# CANageddonBus.net
KiCad netlist of a schematic drawn in EasyEDA
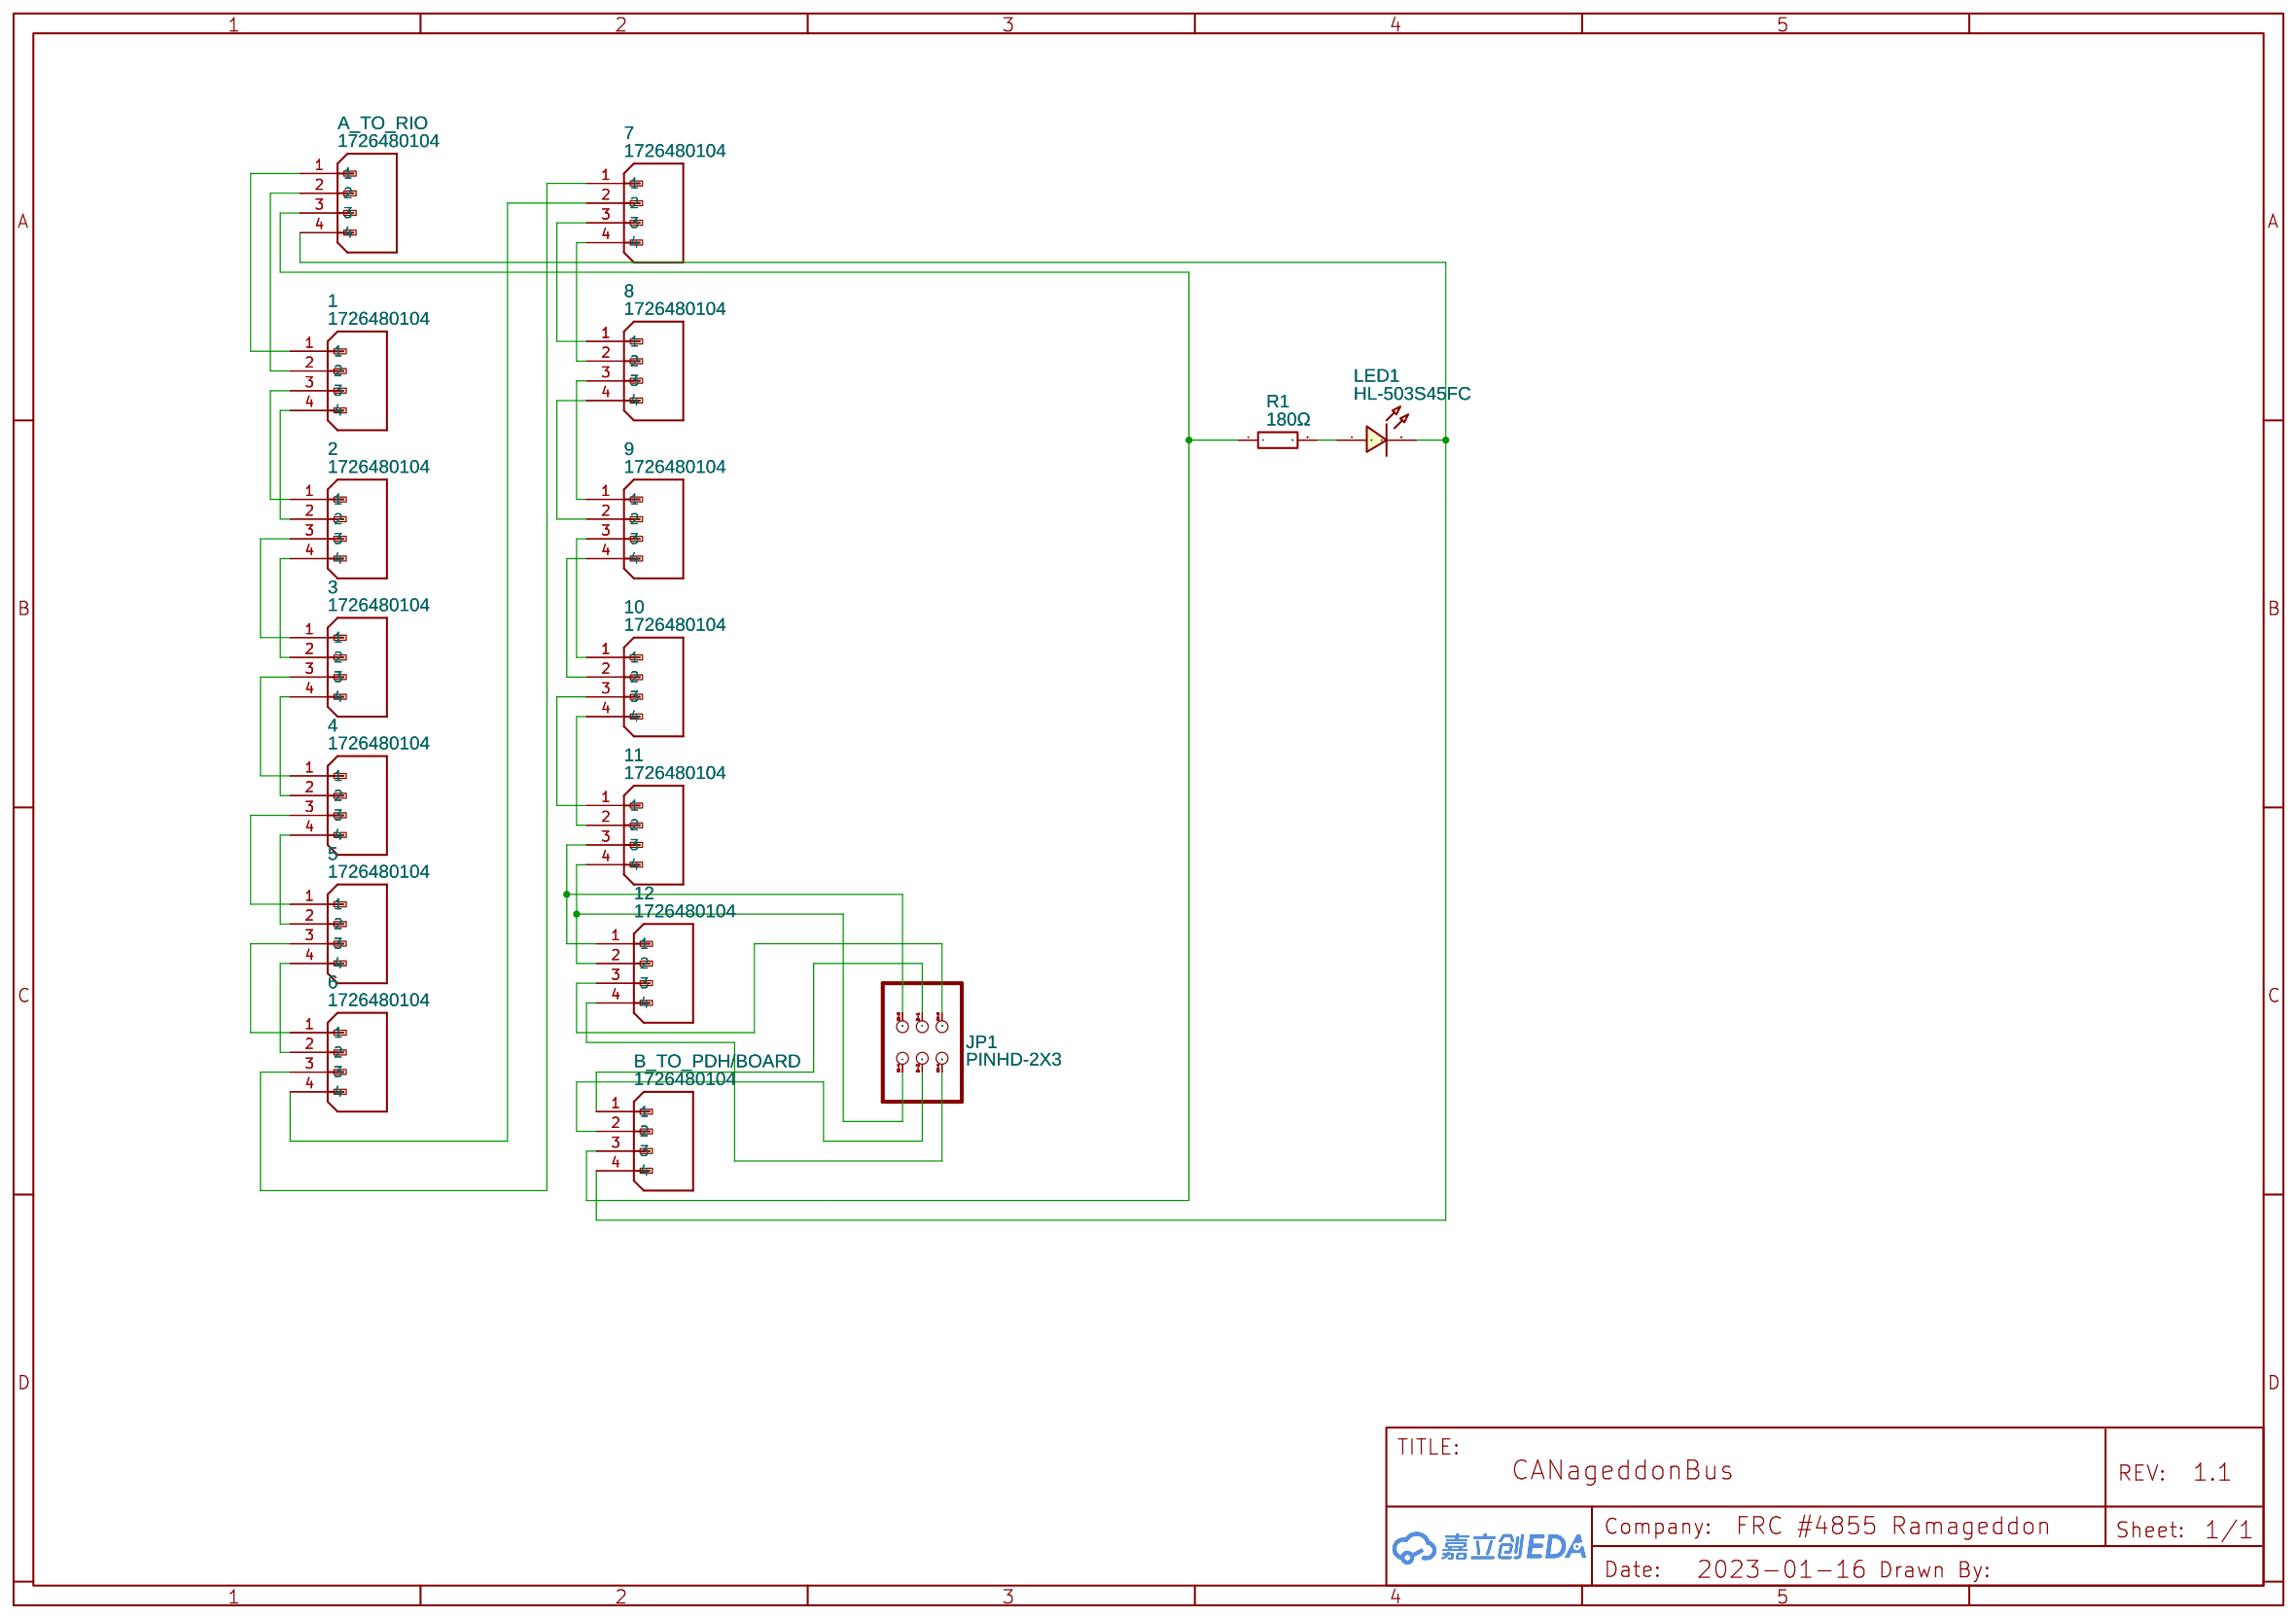
[diagram p0: schematic sheet]

(export (version "E")
  (design (tool "Eeschema 10.0.6"))
  (components
    (comp (ref "1") (value "1726480104") (libsource (lib "") (part "1726480104")))
    (comp (ref "2") (value "1726480104") (libsource (lib "") (part "1726480104")))
    (comp (ref "3") (value "1726480104") (libsource (lib "") (part "1726480104")))
    (comp (ref "4") (value "1726480104") (libsource (lib "") (part "1726480104")))
    (comp (ref "5") (value "1726480104") (libsource (lib "") (part "1726480104")))
    (comp (ref "6") (value "1726480104") (libsource (lib "") (part "1726480104")))
    (comp (ref "7") (value "1726480104") (libsource (lib "") (part "1726480104")))
    (comp (ref "8") (value "1726480104") (libsource (lib "") (part "1726480104")))
    (comp (ref "9") (value "1726480104") (libsource (lib "") (part "1726480104")))
    (comp (ref "10") (value "1726480104") (libsource (lib "") (part "1726480104")))
    (comp (ref "11") (value "1726480104") (libsource (lib "") (part "1726480104")))
    (comp (ref "12") (value "1726480104") (libsource (lib "") (part "1726480104")))
    (comp (ref "A_TO_RIO") (value "1726480104") (libsource (lib "") (part "1726480104_1")))
    (comp (ref "B_TO_PDH/BOARD") (value "1726480104") (libsource (lib "") (part "1726480104_2")))
    (comp (ref "JP1") (value "PINHD-2X3") (libsource (lib "") (part "PINHD-2X3")))
    (comp (ref "LED1")
      (value "HL-503S45FC")
      (fields (field (name "BOM_Supplier Part") "C568942"))
      (libsource (lib "") (part "HL-503S45FC"))
    )
    (comp (ref "R1")
      (value "180Ω")
      (fields
        (field (name "BOM_Manufacturer Part") "MFR0W4F1800A50")
        (field (name "BOM_Supplier Part") "C58665")
      )
      (libsource (lib "") (part "MFR0W4F1800A50"))
    )
  )
  (nets
    (net (code "1") (name "Net-(1-Pad1)") (class "Default")
      (node (ref "1") (pin "1") (pinfunction "1_1") (pintype "bidirectional"))
      (node (ref "A_TO_RIO") (pin "1") (pinfunction "1_1") (pintype "bidirectional"))
    )
    (net (code "2") (name "Net-(1-Pad2)") (class "Default")
      (node (ref "1") (pin "2") (pinfunction "2_2") (pintype "bidirectional"))
      (node (ref "A_TO_RIO") (pin "2") (pinfunction "2_2") (pintype "bidirectional"))
    )
    (net (code "3") (name "Net-(1-Pad3)") (class "Default")
      (node (ref "1") (pin "3") (pinfunction "3_3") (pintype "bidirectional"))
      (node (ref "2") (pin "1") (pinfunction "1_1") (pintype "bidirectional"))
    )
    (net (code "4") (name "Net-(1-Pad4)") (class "Default")
      (node (ref "1") (pin "4") (pinfunction "4_4") (pintype "bidirectional"))
      (node (ref "2") (pin "2") (pinfunction "2_2") (pintype "bidirectional"))
    )
    (net (code "5") (name "Net-(2-Pad3)") (class "Default")
      (node (ref "2") (pin "3") (pinfunction "3_3") (pintype "bidirectional"))
      (node (ref "3") (pin "1") (pinfunction "1_1") (pintype "bidirectional"))
    )
    (net (code "6") (name "Net-(2-Pad4)") (class "Default")
      (node (ref "2") (pin "4") (pinfunction "4_4") (pintype "bidirectional"))
      (node (ref "3") (pin "2") (pinfunction "2_2") (pintype "bidirectional"))
    )
    (net (code "7") (name "Net-(3-Pad3)") (class "Default")
      (node (ref "3") (pin "3") (pinfunction "3_3") (pintype "bidirectional"))
      (node (ref "4") (pin "1") (pinfunction "1_1") (pintype "bidirectional"))
    )
    (net (code "8") (name "Net-(3-Pad4)") (class "Default")
      (node (ref "3") (pin "4") (pinfunction "4_4") (pintype "bidirectional"))
      (node (ref "4") (pin "2") (pinfunction "2_2") (pintype "bidirectional"))
    )
    (net (code "9") (name "Net-(4-Pad3)") (class "Default")
      (node (ref "4") (pin "3") (pinfunction "3_3") (pintype "bidirectional"))
      (node (ref "5") (pin "1") (pinfunction "1_1") (pintype "bidirectional"))
    )
    (net (code "10") (name "Net-(4-Pad4)") (class "Default")
      (node (ref "4") (pin "4") (pinfunction "4_4") (pintype "bidirectional"))
      (node (ref "5") (pin "2") (pinfunction "2_2") (pintype "bidirectional"))
    )
    (net (code "11") (name "Net-(5-Pad3)") (class "Default")
      (node (ref "5") (pin "3") (pinfunction "3_3") (pintype "bidirectional"))
      (node (ref "6") (pin "1") (pinfunction "1_1") (pintype "bidirectional"))
    )
    (net (code "12") (name "Net-(5-Pad4)") (class "Default")
      (node (ref "5") (pin "4") (pinfunction "4_4") (pintype "bidirectional"))
      (node (ref "6") (pin "2") (pinfunction "2_2") (pintype "bidirectional"))
    )
    (net (code "13") (name "Net-(6-Pad3)") (class "Default")
      (node (ref "6") (pin "3") (pinfunction "3_3") (pintype "bidirectional"))
      (node (ref "7") (pin "1") (pinfunction "1_1") (pintype "bidirectional"))
    )
    (net (code "14") (name "Net-(6-Pad4)") (class "Default")
      (node (ref "6") (pin "4") (pinfunction "4_4") (pintype "bidirectional"))
      (node (ref "7") (pin "2") (pinfunction "2_2") (pintype "bidirectional"))
    )
    (net (code "15") (name "Net-(7-Pad3)") (class "Default")
      (node (ref "7") (pin "3") (pinfunction "3_3") (pintype "bidirectional"))
      (node (ref "8") (pin "1") (pinfunction "1_1") (pintype "bidirectional"))
    )
    (net (code "16") (name "Net-(7-Pad4)") (class "Default")
      (node (ref "7") (pin "4") (pinfunction "4_4") (pintype "bidirectional"))
      (node (ref "8") (pin "2") (pinfunction "2_2") (pintype "bidirectional"))
    )
    (net (code "17") (name "Net-(8-Pad3)") (class "Default")
      (node (ref "8") (pin "3") (pinfunction "3_3") (pintype "bidirectional"))
      (node (ref "9") (pin "1") (pinfunction "1_1") (pintype "bidirectional"))
    )
    (net (code "18") (name "Net-(8-Pad4)") (class "Default")
      (node (ref "8") (pin "4") (pinfunction "4_4") (pintype "bidirectional"))
      (node (ref "9") (pin "2") (pinfunction "2_2") (pintype "bidirectional"))
    )
    (net (code "19") (name "Net-(10-Pad1)") (class "Default")
      (node (ref "10") (pin "1") (pinfunction "1_1") (pintype "bidirectional"))
      (node (ref "9") (pin "3") (pinfunction "3_3") (pintype "bidirectional"))
    )
    (net (code "20") (name "Net-(10-Pad2)") (class "Default")
      (node (ref "10") (pin "2") (pinfunction "2_2") (pintype "bidirectional"))
      (node (ref "9") (pin "4") (pinfunction "4_4") (pintype "bidirectional"))
    )
    (net (code "21") (name "Net-(10-Pad3)") (class "Default")
      (node (ref "10") (pin "3") (pinfunction "3_3") (pintype "bidirectional"))
      (node (ref "11") (pin "1") (pinfunction "1_1") (pintype "bidirectional"))
    )
    (net (code "22") (name "Net-(10-Pad4)") (class "Default")
      (node (ref "10") (pin "4") (pinfunction "4_4") (pintype "bidirectional"))
      (node (ref "11") (pin "2") (pinfunction "2_2") (pintype "bidirectional"))
    )
    (net (code "23") (name "Net-(A_TO_RIO-Pad3)") (class "Default")
      (node (ref "A_TO_RIO") (pin "3") (pinfunction "3_3") (pintype "bidirectional"))
      (node (ref "B_TO_PDH/BOARD") (pin "3") (pinfunction "3_3") (pintype "bidirectional"))
      (node (ref "R1") (pin "1") (pinfunction "1_1") (pintype "input"))
    )
    (net (code "24") (name "Net-(A_TO_RIO-Pad4)") (class "Default")
      (node (ref "A_TO_RIO") (pin "4") (pinfunction "4_4") (pintype "bidirectional"))
      (node (ref "B_TO_PDH/BOARD") (pin "4") (pinfunction "4_4") (pintype "bidirectional"))
      (node (ref "LED1") (pin "2") (pinfunction "2_2") (pintype "unspecified"))
    )
    (net (code "25") (name "Net-(JP1-1)") (class "Default")
      (node (ref "11") (pin "4") (pinfunction "4_4") (pintype "bidirectional"))
      (node (ref "12") (pin "2") (pinfunction "2_2") (pintype "bidirectional"))
      (node (ref "JP1") (pin "11-4") (pinfunction "1_11-4") (pintype "unspecified"))
    )
    (net (code "26") (name "Net-(JP1-2)") (class "Default")
      (node (ref "11") (pin "3") (pinfunction "3_3") (pintype "bidirectional"))
      (node (ref "12") (pin "1") (pinfunction "1_1") (pintype "bidirectional"))
      (node (ref "JP1") (pin "11-3") (pinfunction "2_11-3") (pintype "unspecified"))
    )
    (net (code "27") (name "Net-(JP1-3)") (class "Default")
      (node (ref "B_TO_PDH/BOARD") (pin "2") (pinfunction "2_2") (pintype "bidirectional"))
      (node (ref "JP1") (pin "B-2") (pinfunction "3_B-2") (pintype "unspecified"))
    )
    (net (code "28") (name "Net-(JP1-4)") (class "Default")
      (node (ref "B_TO_PDH/BOARD") (pin "1") (pinfunction "1_1") (pintype "bidirectional"))
      (node (ref "JP1") (pin "B-1") (pinfunction "4_B-1") (pintype "unspecified"))
    )
    (net (code "29") (name "Net-(JP1-5)") (class "Default")
      (node (ref "12") (pin "4") (pinfunction "4_4") (pintype "bidirectional"))
      (node (ref "JP1") (pin "12-4") (pinfunction "5_12-4") (pintype "unspecified"))
    )
    (net (code "30") (name "Net-(JP1-6)") (class "Default")
      (node (ref "12") (pin "3") (pinfunction "3_3") (pintype "bidirectional"))
      (node (ref "JP1") (pin "12-3") (pinfunction "6_12-3") (pintype "unspecified"))
    )
    (net (code "31") (name "Net-(LED1-Pad1)") (class "Default")
      (node (ref "LED1") (pin "1") (pinfunction "1_1") (pintype "unspecified"))
      (node (ref "R1") (pin "2") (pinfunction "2_2") (pintype "input"))
    )
  )
)
